# Logic.net
KiCad netlist of a schematic drawn in EAGLE
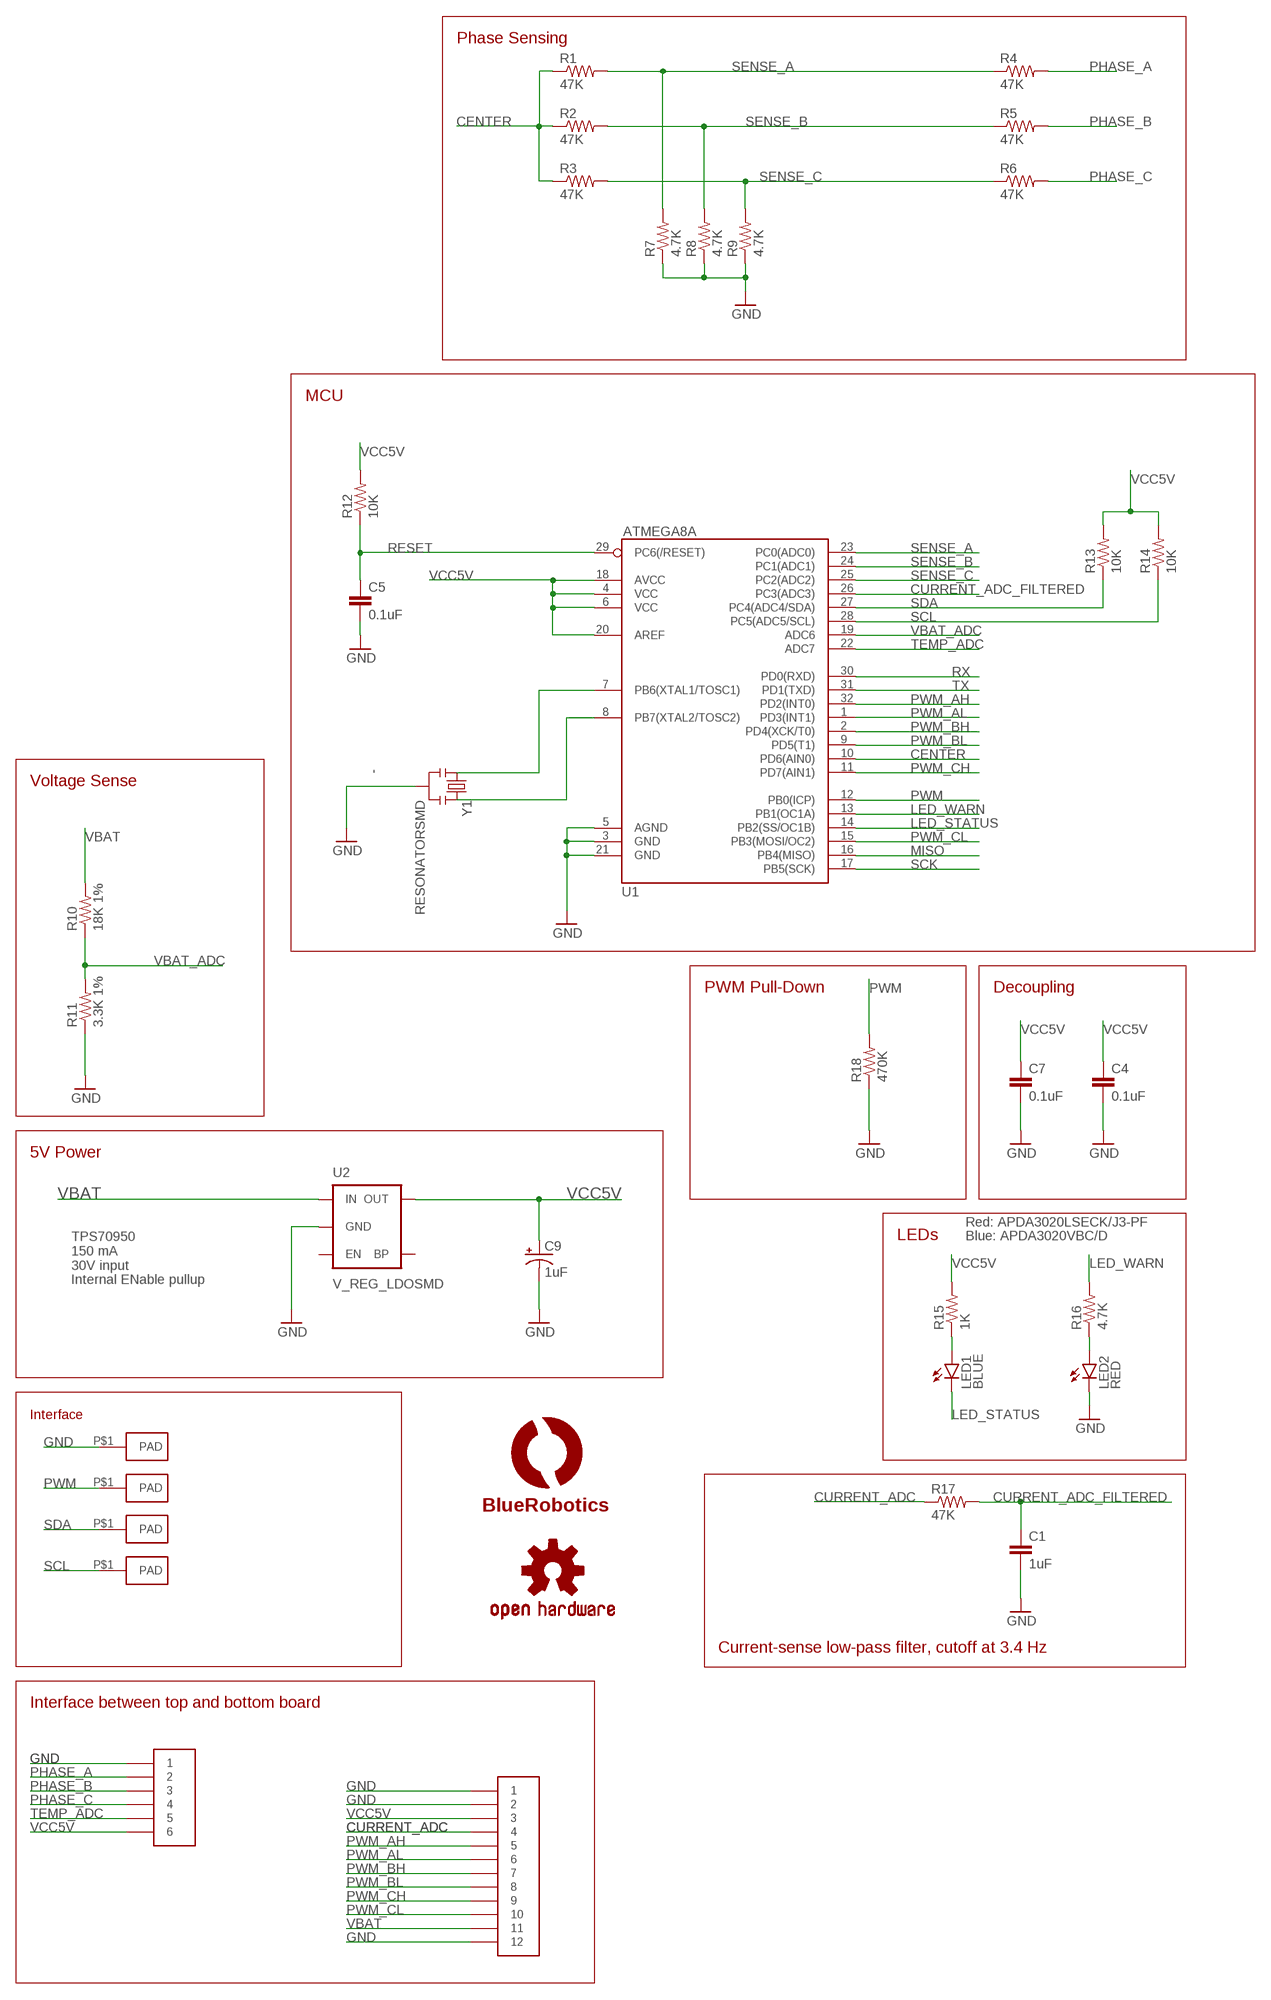
[diagram p0: schematic, sheet 1]

(export (version "E")
  (design (tool "Eeschema 10.0.6"))
  (components
    (comp (ref "C1")
      (value "1uF")
      (footprint "eagle-import:0603-CAP")
      (libsource (lib "eagle-import") (part "CAP0603-CAP"))
    )
    (comp (ref "C4")
      (value "0.1uF")
      (footprint "eagle-import:0603-CAP")
      (libsource (lib "eagle-import") (part "CAP0603-CAP"))
    )
    (comp (ref "C5")
      (value "0.1uF")
      (footprint "eagle-import:0603-CAP")
      (libsource (lib "eagle-import") (part "CAP0603-CAP"))
    )
    (comp (ref "C7")
      (value "0.1uF")
      (footprint "eagle-import:0603-CAP")
      (libsource (lib "eagle-import") (part "CAP0603-CAP"))
    )
    (comp (ref "C9")
      (value "1uF")
      (footprint "eagle-import:EIA3216")
      (libsource (lib "eagle-import") (part "CAP_POL1206"))
    )
    (comp (ref "LED1")
      (value "BLUE")
      (footprint "eagle-import:SMT-LED-3X2-RA")
      (libsource (lib "eagle-import") (part "LED3X2-RA"))
    )
    (comp (ref "LED2")
      (value "RED")
      (footprint "eagle-import:SMT-LED-3X2-RA")
      (libsource (lib "eagle-import") (part "LED3X2-RA"))
    )
    (comp (ref "LOGO1")
      (value "OSHW-LOGOS")
      (footprint "eagle-import:OSHW-LOGO-S")
      (libsource (lib "eagle-import") (part "OSHW-LOGOS"))
    )
    (comp (ref "R1")
      (value "47K")
      (footprint "eagle-import:0603-RES")
      (libsource (lib "eagle-import") (part "33KOHM1/10W1%(0603)"))
    )
    (comp (ref "R2")
      (value "47K")
      (footprint "eagle-import:0603-RES")
      (libsource (lib "eagle-import") (part "33KOHM1/10W1%(0603)"))
    )
    (comp (ref "R3")
      (value "47K")
      (footprint "eagle-import:0603-RES")
      (libsource (lib "eagle-import") (part "33KOHM1/10W1%(0603)"))
    )
    (comp (ref "R4")
      (value "47K")
      (footprint "eagle-import:0603-RES")
      (libsource (lib "eagle-import") (part "33KOHM1/10W1%(0603)"))
    )
    (comp (ref "R5")
      (value "47K")
      (footprint "eagle-import:0603-RES")
      (libsource (lib "eagle-import") (part "33KOHM1/10W1%(0603)"))
    )
    (comp (ref "R6")
      (value "47K")
      (footprint "eagle-import:0603-RES")
      (libsource (lib "eagle-import") (part "33KOHM1/10W1%(0603)"))
    )
    (comp (ref "R7")
      (value "4.7K")
      (footprint "eagle-import:0603-RES")
      (libsource (lib "eagle-import") (part "RESISTOR0603"))
    )
    (comp (ref "R8")
      (value "4.7K")
      (footprint "eagle-import:0603-RES")
      (libsource (lib "eagle-import") (part "RESISTOR0603"))
    )
    (comp (ref "R9")
      (value "4.7K")
      (footprint "eagle-import:0603-RES")
      (libsource (lib "eagle-import") (part "RESISTOR0603"))
    )
    (comp (ref "R10")
      (value "18K 1%")
      (footprint "eagle-import:0603-RES")
      (libsource (lib "eagle-import") (part "33KOHM1/10W1%(0603)"))
    )
    (comp (ref "R11")
      (value "3.3K 1%")
      (footprint "eagle-import:0603-RES")
      (libsource (lib "eagle-import") (part "33KOHM1/10W1%(0603)"))
    )
    (comp (ref "R12")
      (value "10K")
      (footprint "eagle-import:0603-RES")
      (libsource (lib "eagle-import") (part "33KOHM1/10W1%(0603)"))
    )
    (comp (ref "R13")
      (value "10K")
      (footprint "eagle-import:0603-RES")
      (libsource (lib "eagle-import") (part "33KOHM1/10W1%(0603)"))
    )
    (comp (ref "R14")
      (value "10K")
      (footprint "eagle-import:0603-RES")
      (libsource (lib "eagle-import") (part "33KOHM1/10W1%(0603)"))
    )
    (comp (ref "R15")
      (value "1K")
      (footprint "eagle-import:0603-RES")
      (libsource (lib "eagle-import") (part "RESISTOR0603-RES"))
    )
    (comp (ref "R16")
      (value "4.7K")
      (footprint "eagle-import:0603-RES")
      (libsource (lib "eagle-import") (part "RESISTOR0603-RES"))
    )
    (comp (ref "R17")
      (value "47K")
      (footprint "eagle-import:0603-RES")
      (libsource (lib "eagle-import") (part "RESISTOR0603-RES"))
    )
    (comp (ref "R18")
      (value "470K")
      (footprint "eagle-import:0603-RES")
      (libsource (lib "eagle-import") (part "RESISTOR0603-RES"))
    )
    (comp (ref "U$3")
      (value "PAD1.5X3MM")
      (footprint "eagle-import:PAD-1.5X3MM")
      (libsource (lib "eagle-import") (part "PAD1.5X3MM"))
    )
    (comp (ref "U$4")
      (value "LOGOBR-LOGO-M")
      (footprint "eagle-import:BR-LOGO-MEDIUM")
      (libsource (lib "eagle-import") (part "LOGOBR-LOGO-M"))
    )
    (comp (ref "U$9")
      (value "PAD1.5X3MM")
      (footprint "eagle-import:PAD-1.5X3MM")
      (libsource (lib "eagle-import") (part "PAD1.5X3MM"))
    )
    (comp (ref "U$10")
      (value "PAD1.5X3MM")
      (footprint "eagle-import:PAD-1.5X3MM")
      (libsource (lib "eagle-import") (part "PAD1.5X3MM"))
    )
    (comp (ref "U$11")
      (value "PAD1.5X3MM")
      (footprint "eagle-import:PAD-1.5X3MM")
      (libsource (lib "eagle-import") (part "PAD1.5X3MM"))
    )
    (comp (ref "U$16")
      (value "HEADER-62MM")
      (footprint "eagle-import:HEADER-2MM-6POS")
      (libsource (lib "eagle-import") (part "HEADER-62MM"))
    )
    (comp (ref "U$17")
      (value "HEADER-122MM")
      (footprint "eagle-import:HEADER-2MM-12POS")
      (libsource (lib "eagle-import") (part "HEADER-122MM"))
    )
    (comp (ref "U1")
      (value "ATMEGA168")
      (footprint "eagle-import:TQFP32-08")
      (libsource (lib "eagle-import") (part "ATMEGA168"))
    )
    (comp (ref "U2")
      (value "V_REG_LDOSMD")
      (footprint "eagle-import:SOT23-5")
      (libsource (lib "eagle-import") (part "V_REG_LDOSMD"))
    )
    (comp (ref "Y1")
      (value "RESONATORSMD")
      (footprint "eagle-import:RESONATOR-SMD")
      (libsource (lib "eagle-import") (part "RESONATORSMD"))
    )
  )
  (nets
    (net (code "1") (name "/CENTER") (class "Default")
      (node (ref "R1") (pin "1") (pinfunction "1_1") (pintype "passive"))
      (node (ref "R2") (pin "1") (pinfunction "1_1") (pintype "passive"))
      (node (ref "R3") (pin "1") (pinfunction "1_1") (pintype "passive"))
      (node (ref "U1") (pin "10") (pinfunction "PD6(AIN0)_10") (pintype "bidirectional"))
    )
    (net (code "2") (name "/CURRENT_ADC") (class "Default")
      (node (ref "R17") (pin "1") (pinfunction "1_1") (pintype "passive"))
      (node (ref "U$17") (pin "P$4") (pinfunction "4_P$4") (pintype "bidirectional"))
    )
    (net (code "3") (name "/CURRENT_ADC_FILTERED") (class "Default")
      (node (ref "C1") (pin "1") (pinfunction "1_1") (pintype "passive"))
      (node (ref "R17") (pin "2") (pinfunction "2_2") (pintype "passive"))
      (node (ref "U1") (pin "26") (pinfunction "PC3(ADC3)_26") (pintype "bidirectional"))
    )
    (net (code "4") (name "/LED_STATUS") (class "Default")
      (node (ref "LED1") (pin "2") (pinfunction "C_2") (pintype "passive"))
      (node (ref "U1") (pin "14") (pinfunction "PB2(SS/OC1B)_14") (pintype "bidirectional"))
    )
    (net (code "5") (name "/LED_WARN") (class "Default")
      (node (ref "R16") (pin "2") (pinfunction "2_2") (pintype "passive"))
      (node (ref "U1") (pin "13") (pinfunction "PB1(OC1A)_13") (pintype "bidirectional"))
    )
    (net (code "6") (name "/MISO") (class "Default")
      (node (ref "U1") (pin "16") (pinfunction "PB4(MISO)_16") (pintype "bidirectional"))
    )
    (net (code "7") (name "/PHASE_A") (class "Default")
      (node (ref "R4") (pin "2") (pinfunction "2_2") (pintype "passive"))
      (node (ref "U$16") (pin "P$2") (pinfunction "2_P$2") (pintype "bidirectional"))
    )
    (net (code "8") (name "/PHASE_B") (class "Default")
      (node (ref "R5") (pin "2") (pinfunction "2_2") (pintype "passive"))
      (node (ref "U$16") (pin "P$3") (pinfunction "3_P$3") (pintype "bidirectional"))
    )
    (net (code "9") (name "/PHASE_C") (class "Default")
      (node (ref "R6") (pin "2") (pinfunction "2_2") (pintype "passive"))
      (node (ref "U$16") (pin "P$4") (pinfunction "4_P$4") (pintype "bidirectional"))
    )
    (net (code "10") (name "/PWM") (class "Default")
      (node (ref "R18") (pin "2") (pinfunction "2_2") (pintype "passive"))
      (node (ref "U$11") (pin "P$1") (pinfunction "PAD_P$1") (pintype "bidirectional"))
      (node (ref "U1") (pin "12") (pinfunction "PB0(ICP)_12") (pintype "bidirectional"))
    )
    (net (code "11") (name "/PWM_AH") (class "Default")
      (node (ref "U$17") (pin "P$5") (pinfunction "5_P$5") (pintype "bidirectional"))
      (node (ref "U1") (pin "32") (pinfunction "PD2(INT0)_32") (pintype "bidirectional"))
    )
    (net (code "12") (name "/PWM_AL") (class "Default")
      (node (ref "U$17") (pin "P$6") (pinfunction "6_P$6") (pintype "bidirectional"))
      (node (ref "U1") (pin "1") (pinfunction "PD3(INT1)_1") (pintype "bidirectional"))
    )
    (net (code "13") (name "/PWM_BH") (class "Default")
      (node (ref "U$17") (pin "P$7") (pinfunction "7_P$7") (pintype "bidirectional"))
      (node (ref "U1") (pin "2") (pinfunction "PD4(XCK/T0)_2") (pintype "bidirectional"))
    )
    (net (code "14") (name "/PWM_BL") (class "Default")
      (node (ref "U$17") (pin "P$8") (pinfunction "8_P$8") (pintype "bidirectional"))
      (node (ref "U1") (pin "9") (pinfunction "PD5(T1)_9") (pintype "bidirectional"))
    )
    (net (code "15") (name "/PWM_CH") (class "Default")
      (node (ref "U$17") (pin "P$9") (pinfunction "9_P$9") (pintype "bidirectional"))
      (node (ref "U1") (pin "11") (pinfunction "PD7(AIN1)_11") (pintype "bidirectional"))
    )
    (net (code "16") (name "/PWM_CL") (class "Default")
      (node (ref "U$17") (pin "P$10") (pinfunction "10_P$10") (pintype "bidirectional"))
      (node (ref "U1") (pin "15") (pinfunction "PB3(MOSI/OC2)_15") (pintype "bidirectional"))
    )
    (net (code "17") (name "/RESET") (class "Default")
      (node (ref "C5") (pin "1") (pinfunction "1_1") (pintype "passive"))
      (node (ref "R12") (pin "1") (pinfunction "1_1") (pintype "passive"))
      (node (ref "U1") (pin "29") (pinfunction "PC6(/RESET)_29") (pintype "bidirectional"))
    )
    (net (code "18") (name "/RX") (class "Default")
      (node (ref "U1") (pin "30") (pinfunction "PD0(RXD)_30") (pintype "bidirectional"))
    )
    (net (code "19") (name "/SCK") (class "Default")
      (node (ref "U1") (pin "17") (pinfunction "PB5(SCK)_17") (pintype "bidirectional"))
    )
    (net (code "20") (name "/SCL") (class "Default")
      (node (ref "R14") (pin "1") (pinfunction "1_1") (pintype "passive"))
      (node (ref "U$10") (pin "P$1") (pinfunction "PAD_P$1") (pintype "bidirectional"))
      (node (ref "U1") (pin "28") (pinfunction "PC5(ADC5/SCL)_28") (pintype "bidirectional"))
    )
    (net (code "21") (name "/SDA") (class "Default")
      (node (ref "R13") (pin "1") (pinfunction "1_1") (pintype "passive"))
      (node (ref "U$9") (pin "P$1") (pinfunction "PAD_P$1") (pintype "bidirectional"))
      (node (ref "U1") (pin "27") (pinfunction "PC4(ADC4/SDA)_27") (pintype "bidirectional"))
    )
    (net (code "22") (name "/SENSE_A") (class "Default")
      (node (ref "R1") (pin "2") (pinfunction "2_2") (pintype "passive"))
      (node (ref "R4") (pin "1") (pinfunction "1_1") (pintype "passive"))
      (node (ref "R7") (pin "2") (pinfunction "2_2") (pintype "passive"))
      (node (ref "U1") (pin "23") (pinfunction "PC0(ADC0)_23") (pintype "bidirectional"))
    )
    (net (code "23") (name "/SENSE_B") (class "Default")
      (node (ref "R2") (pin "2") (pinfunction "2_2") (pintype "passive"))
      (node (ref "R5") (pin "1") (pinfunction "1_1") (pintype "passive"))
      (node (ref "R8") (pin "2") (pinfunction "2_2") (pintype "passive"))
      (node (ref "U1") (pin "24") (pinfunction "PC1(ADC1)_24") (pintype "bidirectional"))
    )
    (net (code "24") (name "/SENSE_C") (class "Default")
      (node (ref "R3") (pin "2") (pinfunction "2_2") (pintype "passive"))
      (node (ref "R6") (pin "1") (pinfunction "1_1") (pintype "passive"))
      (node (ref "R9") (pin "2") (pinfunction "2_2") (pintype "passive"))
      (node (ref "U1") (pin "25") (pinfunction "PC2(ADC2)_25") (pintype "bidirectional"))
    )
    (net (code "25") (name "/TEMP_ADC") (class "Default")
      (node (ref "U$16") (pin "P$5") (pinfunction "5_P$5") (pintype "bidirectional"))
      (node (ref "U1") (pin "22") (pinfunction "ADC7_22") (pintype "bidirectional"))
    )
    (net (code "26") (name "/TX") (class "Default")
      (node (ref "U1") (pin "31") (pinfunction "PD1(TXD)_31") (pintype "bidirectional"))
    )
    (net (code "27") (name "/VBAT") (class "Default")
      (node (ref "R10") (pin "2") (pinfunction "2_2") (pintype "passive"))
      (node (ref "U$17") (pin "P$11") (pinfunction "11_P$11") (pintype "bidirectional"))
      (node (ref "U2") (pin "1") (pinfunction "IN_1") (pintype "input"))
    )
    (net (code "28") (name "/VBAT_ADC") (class "Default")
      (node (ref "R10") (pin "1") (pinfunction "1_1") (pintype "passive"))
      (node (ref "R11") (pin "2") (pinfunction "2_2") (pintype "passive"))
      (node (ref "U1") (pin "19") (pinfunction "ADC6_19") (pintype "bidirectional"))
    )
    (net (code "29") (name "/VCC5V") (class "Default")
      (node (ref "C4") (pin "1") (pinfunction "1_1") (pintype "passive"))
      (node (ref "C7") (pin "1") (pinfunction "1_1") (pintype "passive"))
      (node (ref "C9") (pin "A") (pinfunction "+_A") (pintype "passive"))
      (node (ref "R12") (pin "2") (pinfunction "2_2") (pintype "passive"))
      (node (ref "R13") (pin "2") (pinfunction "2_2") (pintype "passive"))
      (node (ref "R14") (pin "2") (pinfunction "2_2") (pintype "passive"))
      (node (ref "R15") (pin "2") (pinfunction "2_2") (pintype "passive"))
      (node (ref "U$16") (pin "P$6") (pinfunction "6_P$6") (pintype "bidirectional"))
      (node (ref "U$17") (pin "P$3") (pinfunction "3_P$3") (pintype "bidirectional"))
      (node (ref "U1") (pin "18") (pinfunction "AVCC_18") (pintype "bidirectional"))
      (node (ref "U1") (pin "20") (pinfunction "AREF_20") (pintype "bidirectional"))
      (node (ref "U1") (pin "4") (pinfunction "VCC_4") (pintype "bidirectional"))
      (node (ref "U1") (pin "6") (pinfunction "VCC_6") (pintype "bidirectional"))
      (node (ref "U2") (pin "5") (pinfunction "OUT_5") (pintype "passive"))
    )
    (net (code "30") (name "GND") (class "Default")
      (node (ref "C1") (pin "2") (pinfunction "2_2") (pintype "passive"))
      (node (ref "C4") (pin "2") (pinfunction "2_2") (pintype "passive"))
      (node (ref "C5") (pin "2") (pinfunction "2_2") (pintype "passive"))
      (node (ref "C7") (pin "2") (pinfunction "2_2") (pintype "passive"))
      (node (ref "C9") (pin "C") (pinfunction "-_C") (pintype "passive"))
      (node (ref "LED2") (pin "2") (pinfunction "C_2") (pintype "passive"))
      (node (ref "R11") (pin "1") (pinfunction "1_1") (pintype "passive"))
      (node (ref "R18") (pin "1") (pinfunction "1_1") (pintype "passive"))
      (node (ref "R7") (pin "1") (pinfunction "1_1") (pintype "passive"))
      (node (ref "R8") (pin "1") (pinfunction "1_1") (pintype "passive"))
      (node (ref "R9") (pin "1") (pinfunction "1_1") (pintype "passive"))
      (node (ref "U$16") (pin "P$1") (pinfunction "1_P$1") (pintype "bidirectional"))
      (node (ref "U$17") (pin "P$1") (pinfunction "1_P$1") (pintype "bidirectional"))
      (node (ref "U$17") (pin "P$12") (pinfunction "12_P$12") (pintype "bidirectional"))
      (node (ref "U$17") (pin "P$2") (pinfunction "2_P$2") (pintype "bidirectional"))
      (node (ref "U$3") (pin "P$1") (pinfunction "PAD_P$1") (pintype "bidirectional"))
      (node (ref "U1") (pin "21") (pinfunction "GND_21") (pintype "bidirectional"))
      (node (ref "U1") (pin "3") (pinfunction "GND_3") (pintype "bidirectional"))
      (node (ref "U1") (pin "5") (pinfunction "AGND_5") (pintype "bidirectional"))
      (node (ref "U2") (pin "2") (pinfunction "GND_2") (pintype "input"))
      (node (ref "Y1") (pin "2") (pinfunction "2_2") (pintype "passive"))
    )
    (net (code "31") (name "Net-(LED1-A)") (class "Default")
      (node (ref "LED1") (pin "1") (pinfunction "A_1") (pintype "passive"))
      (node (ref "R15") (pin "1") (pinfunction "1_1") (pintype "passive"))
    )
    (net (code "32") (name "Net-(LED2-A)") (class "Default")
      (node (ref "LED2") (pin "1") (pinfunction "A_1") (pintype "passive"))
      (node (ref "R16") (pin "1") (pinfunction "1_1") (pintype "passive"))
    )
    (net (code "33") (name "Net-(U1-PB6(XTAL1{slash}TOSC1))") (class "Default")
      (node (ref "U1") (pin "7") (pinfunction "PB6(XTAL1/TOSC1)_7") (pintype "bidirectional"))
      (node (ref "Y1") (pin "1") (pinfunction "1_1") (pintype "passive"))
    )
    (net (code "34") (name "Net-(U1-PB7(XTAL2{slash}TOSC2))") (class "Default")
      (node (ref "U1") (pin "8") (pinfunction "PB7(XTAL2/TOSC2)_8") (pintype "bidirectional"))
      (node (ref "Y1") (pin "3") (pinfunction "3_3") (pintype "passive"))
    )
    (net (code "35") (name "unconnected-(U2-BP-Pad4)") (class "Default")
      (node (ref "U2") (pin "4") (pinfunction "BP_4") (pintype "input"))
    )
    (net (code "36") (name "unconnected-(U2-EN-Pad3)") (class "Default")
      (node (ref "U2") (pin "3") (pinfunction "EN_3") (pintype "input"))
    )
  )
)
